# DriverCircuit.net
KiCad netlist of a schematic drawn in Altium Designer
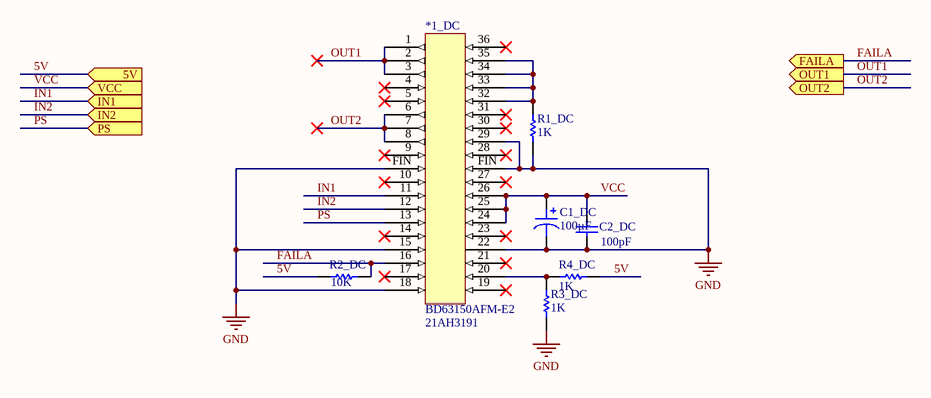
[diagram p0: DriverCircuit.SchDoc]

(export (version "E")
  (design (tool "Eeschema 10.0.6"))
  (components
    (comp (ref "*1_DC")
      (value "BD63150AFM-E2")
      (footprint "Rohm_HSOP-M36_MFG")
      (description "DC Driver")
      (fields (field (name "SUPPLIER PART NUMBER 1") "21AH3191"))
      (libsource (lib "Lib") (part "BD63150AFM-E2"))
    )
    (comp (ref "C1_DC")
      (value "100µF")
      (footprint "CAP ALSMD 6.6MM H6.1MM")
      (description "CAP ALUM 100UF 20% 10V SMD")
      (fields (field (name "PART NUMBER") "UWZ1A101MCL1GB") (field (name "MANUFACTURER") "Nichicon"))
      (libsource (lib "Celestial Altium Library - altium_library (5)") (part "Polarised Capacitor"))
    )
    (comp (ref "C2_DC")
      (value "100pF")
      (footprint "1608[0603]")
      (description "Capacitor")
      (fields (field (name "Comment") "Cap") (field (name "PUBLISHER") "Altium Limited"))
      (libsource (lib "Miscellaneous Devices") (part "Cap"))
    )
    (comp (ref "R1_DC")
      (value "1K")
      (footprint "1608[0603]")
      (description "Resistor")
      (fields (field (name "Comment") "Res1") (field (name "PUBLISHER") "Altium Limited"))
      (libsource (lib "Miscellaneous Devices") (part "Res1"))
    )
    (comp (ref "R2_DC")
      (value "10K")
      (footprint "1608[0603]")
      (description "Resistor")
      (fields (field (name "Comment") "Res1") (field (name "PUBLISHER") "Altium Limited"))
      (libsource (lib "Miscellaneous Devices") (part "Res1"))
    )
    (comp (ref "R3_DC")
      (value "1K")
      (footprint "1608[0603]")
      (description "Resistor")
      (fields (field (name "Comment") "Res1") (field (name "PUBLISHER") "Altium Limited"))
      (libsource (lib "Miscellaneous Devices") (part "Res1"))
    )
    (comp (ref "R4_DC")
      (value "1K")
      (footprint "1608[0603]")
      (description "Resistor")
      (fields (field (name "Comment") "Res1") (field (name "PUBLISHER") "Altium Limited"))
      (libsource (lib "Miscellaneous Devices") (part "Res1"))
    )
  )
  (nets
    (net (code "1") (name "/5V") (class "Default")
      (node (ref "R2_DC") (pin "1") (pinfunction "1_1") (pintype "passive"))
      (node (ref "R4_DC") (pin "1") (pinfunction "1_1") (pintype "passive"))
    )
    (net (code "2") (name "/FAILA") (class "Default")
      (node (ref "*1_DC") (pin "16") (pintype "input"))
      (node (ref "R2_DC") (pin "2") (pinfunction "2_2") (pintype "passive"))
    )
    (net (code "3") (name "/IN1") (class "Default") (node (ref "*1_DC") (pin "11") (pintype "input")))
    (net (code "4") (name "/IN2") (class "Default") (node (ref "*1_DC") (pin "12") (pintype "input")))
    (net (code "5") (name "/OUT1") (class "Default")
      (node (ref "*1_DC") (pin "1") (pintype "output"))
      (node (ref "*1_DC") (pin "2") (pintype "output"))
      (node (ref "*1_DC") (pin "3") (pintype "output"))
    )
    (net (code "6") (name "/OUT2") (class "Default")
      (node (ref "*1_DC") (pin "6") (pintype "output"))
      (node (ref "*1_DC") (pin "7") (pintype "output"))
      (node (ref "*1_DC") (pin "8") (pintype "output"))
    )
    (net (code "7") (name "/PS") (class "Default") (node (ref "*1_DC") (pin "13") (pintype "input")))
    (net (code "8") (name "/VCC") (class "Default")
      (node (ref "*1_DC") (pin "24") (pintype "input"))
      (node (ref "*1_DC") (pin "25") (pintype "input"))
      (node (ref "*1_DC") (pin "26") (pintype "input"))
      (node (ref "C1_DC") (pin "1") (pinfunction "1_1") (pintype "passive"))
      (node (ref "C2_DC") (pin "2") (pinfunction "2_2") (pintype "passive"))
    )
    (net (code "9") (name "GND") (class "Default")
      (node (ref "*1_DC") (pin "15") (pintype "input"))
      (node (ref "*1_DC") (pin "18") (pintype "input"))
      (node (ref "*1_DC") (pin "22") (pintype "passive"))
      (node (ref "*1_DC") (pin "29") (pintype "input"))
      (node (ref "*1_DC") (pin "FIN") (pintype "input"))
      (node (ref "C1_DC") (pin "2") (pinfunction "2_2") (pintype "passive"))
      (node (ref "C2_DC") (pin "1") (pinfunction "1_1") (pintype "passive"))
      (node (ref "R1_DC") (pin "2") (pinfunction "2_2") (pintype "passive"))
      (node (ref "R3_DC") (pin "2") (pinfunction "2_2") (pintype "passive"))
    )
    (net (code "10") (name "Net-(*1_DC-Pad20)") (class "Default")
      (node (ref "*1_DC") (pin "20") (pintype "input"))
      (node (ref "R3_DC") (pin "1") (pinfunction "1_1") (pintype "passive"))
      (node (ref "R4_DC") (pin "2") (pinfunction "2_2") (pintype "passive"))
    )
    (net (code "11") (name "Net-(*1_DC-Pad32)") (class "Default")
      (node (ref "*1_DC") (pin "32") (pintype "input"))
      (node (ref "*1_DC") (pin "33") (pintype "input"))
      (node (ref "*1_DC") (pin "34") (pintype "input"))
      (node (ref "*1_DC") (pin "35") (pintype "input"))
      (node (ref "R1_DC") (pin "1") (pinfunction "1_1") (pintype "passive"))
    )
    (net (code "12") (name "unconnected-(*1_DC-Pad4)") (class "Default")
      (node (ref "*1_DC") (pin "4") (pintype "input+no_connect"))
    )
    (net (code "13") (name "unconnected-(*1_DC-Pad5)") (class "Default")
      (node (ref "*1_DC") (pin "5") (pintype "input+no_connect"))
    )
    (net (code "14") (name "unconnected-(*1_DC-Pad9)") (class "Default")
      (node (ref "*1_DC") (pin "9") (pintype "input+no_connect"))
    )
    (net (code "15") (name "unconnected-(*1_DC-Pad10)") (class "Default")
      (node (ref "*1_DC") (pin "10") (pintype "input+no_connect"))
    )
    (net (code "16") (name "unconnected-(*1_DC-Pad14)") (class "Default")
      (node (ref "*1_DC") (pin "14") (pintype "input+no_connect"))
    )
    (net (code "17") (name "unconnected-(*1_DC-Pad17)") (class "Default")
      (node (ref "*1_DC") (pin "17") (pintype "input+no_connect"))
    )
    (net (code "18") (name "unconnected-(*1_DC-Pad19)") (class "Default")
      (node (ref "*1_DC") (pin "19") (pintype "input+no_connect"))
    )
    (net (code "19") (name "unconnected-(*1_DC-Pad21)") (class "Default")
      (node (ref "*1_DC") (pin "21") (pintype "input+no_connect"))
    )
    (net (code "20") (name "unconnected-(*1_DC-Pad23)") (class "Default")
      (node (ref "*1_DC") (pin "23") (pintype "input+no_connect"))
    )
    (net (code "21") (name "unconnected-(*1_DC-Pad27)") (class "Default")
      (node (ref "*1_DC") (pin "27") (pintype "input+no_connect"))
    )
    (net (code "22") (name "unconnected-(*1_DC-Pad28)") (class "Default")
      (node (ref "*1_DC") (pin "28") (pintype "input+no_connect"))
    )
    (net (code "23") (name "unconnected-(*1_DC-Pad30)") (class "Default")
      (node (ref "*1_DC") (pin "30") (pintype "input+no_connect"))
    )
    (net (code "24") (name "unconnected-(*1_DC-Pad31)") (class "Default")
      (node (ref "*1_DC") (pin "31") (pintype "input+no_connect"))
    )
    (net (code "25") (name "unconnected-(*1_DC-Pad36)") (class "Default")
      (node (ref "*1_DC") (pin "36") (pintype "input+no_connect"))
    )
  )
)
